# untitled.net
KiCad netlist of a schematic drawn in EAGLE
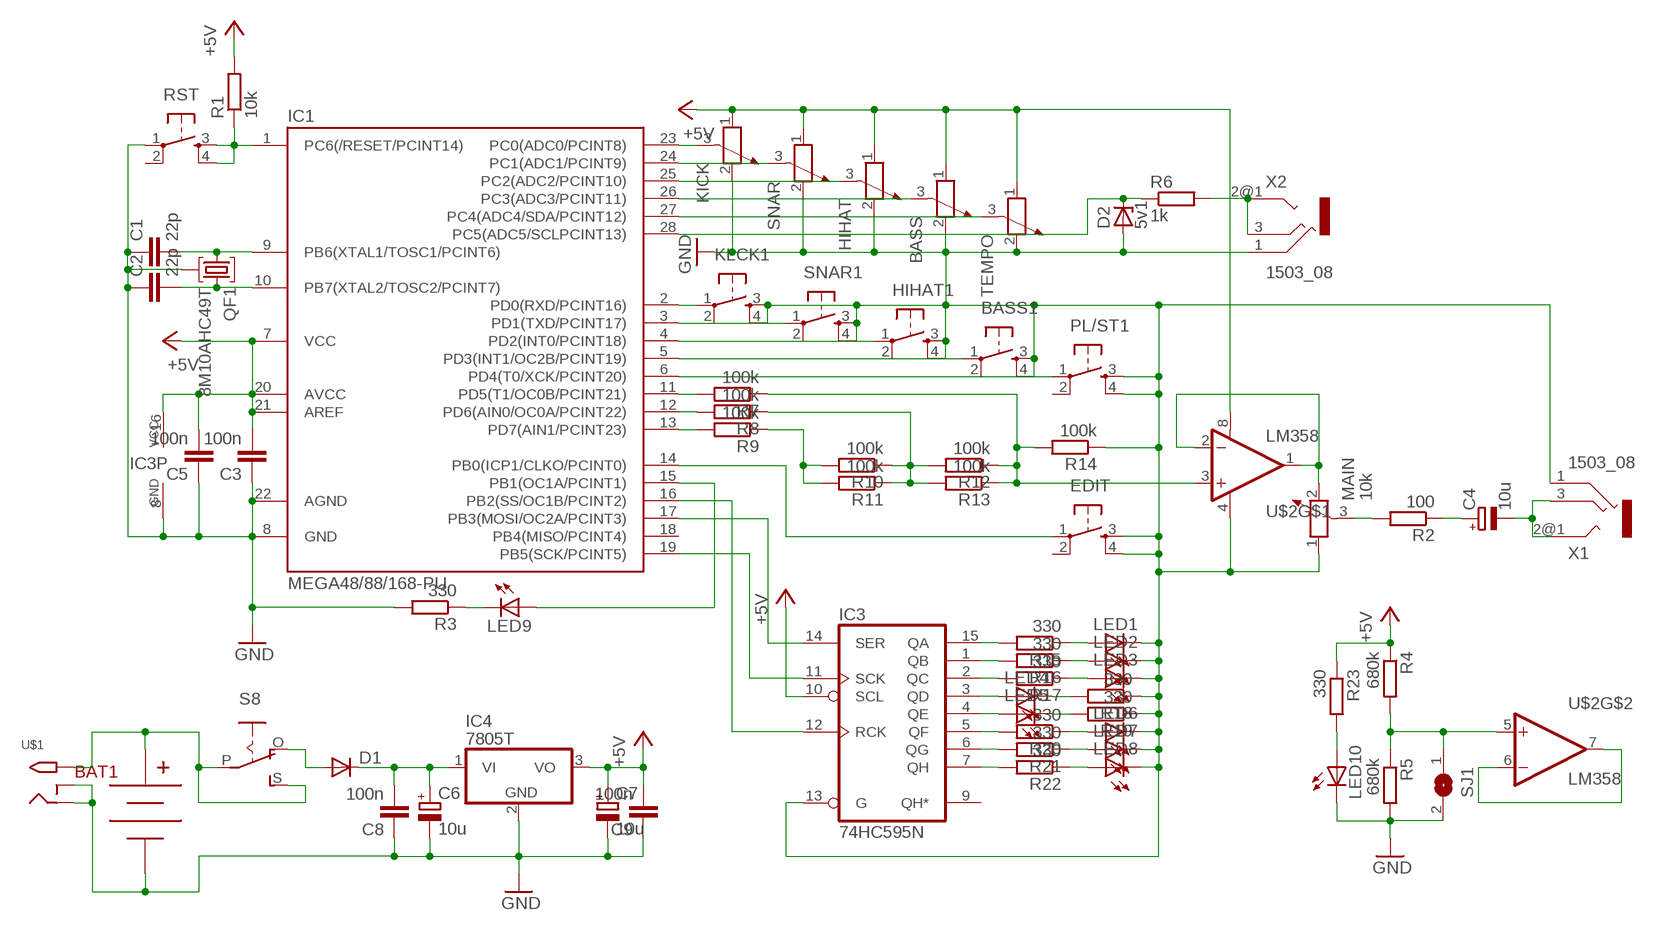
[diagram p0: schematic, sheet 1]

(export (version "E")
  (design (tool "Eeschema 10.0.6"))
  (components
    (comp (ref "BASS")
      (value "POTENTIOMETER_PT-10")
      (footprint "eagle-import:PT-10")
      (libsource (lib "eagle-import") (part "POTENTIOMETER_PT-10"))
    )
    (comp (ref "BASS1")
      (value "TAC_SWITCHPTH")
      (footprint "eagle-import:TACTILE-PTH")
      (libsource (lib "eagle-import") (part "TAC_SWITCHPTH"))
    )
    (comp (ref "BAT1")
      (value "BC9VPC")
      (footprint "eagle-import:BC9VPC")
      (libsource (lib "eagle-import") (part "BC9VPC"))
    )
    (comp (ref "C1")
      (value "22p")
      (footprint "eagle-import:C025-025X050")
      (libsource (lib "eagle-import") (part "C-EU025-025X050"))
    )
    (comp (ref "C2")
      (value "22p")
      (footprint "eagle-import:C025-025X050")
      (libsource (lib "eagle-import") (part "C-EU025-025X050"))
    )
    (comp (ref "C3")
      (value "100n")
      (footprint "eagle-import:C025-025X050")
      (libsource (lib "eagle-import") (part "C-EU025-025X050"))
    )
    (comp (ref "C4")
      (value "10u")
      (footprint "eagle-import:E2,5-6")
      (libsource (lib "eagle-import") (part "CPOL-EUE2.5-6"))
    )
    (comp (ref "C5")
      (value "100n")
      (footprint "eagle-import:C025-025X050")
      (libsource (lib "eagle-import") (part "C-EU025-025X050"))
    )
    (comp (ref "C6")
      (value "10u")
      (footprint "eagle-import:E2,5-5")
      (libsource (lib "eagle-import") (part "CPOL-EUE2.5-5"))
    )
    (comp (ref "C7")
      (value "10u")
      (footprint "eagle-import:E2,5-5")
      (libsource (lib "eagle-import") (part "CPOL-EUE2.5-5"))
    )
    (comp (ref "C8")
      (value "100n")
      (footprint "eagle-import:C025-025X050")
      (libsource (lib "eagle-import") (part "C-EU025-025X050"))
    )
    (comp (ref "C9")
      (value "100n")
      (footprint "eagle-import:C025-025X050")
      (libsource (lib "eagle-import") (part "C-EU025-025X050"))
    )
    (comp (ref "D1")
      (value "DIODE-D-5")
      (footprint "eagle-import:D-5")
      (libsource (lib "eagle-import") (part "DIODE-D-5"))
    )
    (comp (ref "D2")
      (value "5v1")
      (footprint "eagle-import:ZDIO-2.5")
      (libsource (lib "eagle-import") (part "ZENER-DIODEZD-2.5"))
    )
    (comp (ref "EDIT")
      (value "TAC_SWITCHPTH")
      (footprint "eagle-import:TACTILE-PTH")
      (libsource (lib "eagle-import") (part "TAC_SWITCHPTH"))
    )
    (comp (ref "HIHAT")
      (value "POTENTIOMETER_PT-10")
      (footprint "eagle-import:PT-10")
      (libsource (lib "eagle-import") (part "POTENTIOMETER_PT-10"))
    )
    (comp (ref "HIHAT1")
      (value "TAC_SWITCHPTH")
      (footprint "eagle-import:TACTILE-PTH")
      (libsource (lib "eagle-import") (part "TAC_SWITCHPTH"))
    )
    (comp (ref "IC1")
      (value "MEGA48/88/168-PU")
      (footprint "eagle-import:DIL28-3")
      (libsource (lib "eagle-import") (part "MEGA48/88/168-PU"))
    )
    (comp (ref "IC3")
      (value "74HC595N")
      (footprint "eagle-import:DIL16")
      (libsource (lib "eagle-import") (part "74595NHC"))
    )
    (comp (ref "IC4")
      (value "7805T")
      (footprint "eagle-import:TO220H")
      (libsource (lib "eagle-import") (part "78T05"))
    )
    (comp (ref "KICK")
      (value "POTENTIOMETER_PT-10")
      (footprint "eagle-import:PT-10")
      (libsource (lib "eagle-import") (part "POTENTIOMETER_PT-10"))
    )
    (comp (ref "KLCK1")
      (value "TAC_SWITCHPTH")
      (footprint "eagle-import:TACTILE-PTH")
      (libsource (lib "eagle-import") (part "TAC_SWITCHPTH"))
    )
    (comp (ref "LED1")
      (value "LED5MM")
      (footprint "eagle-import:LED5MM")
      (libsource (lib "eagle-import") (part "LED5MM"))
    )
    (comp (ref "LED2")
      (value "LED5MM")
      (footprint "eagle-import:LED5MM")
      (libsource (lib "eagle-import") (part "LED5MM"))
    )
    (comp (ref "LED3")
      (value "LED5MM")
      (footprint "eagle-import:LED5MM")
      (libsource (lib "eagle-import") (part "LED5MM"))
    )
    (comp (ref "LED4")
      (value "LED5MM")
      (footprint "eagle-import:LED5MM")
      (libsource (lib "eagle-import") (part "LED5MM"))
    )
    (comp (ref "LED5")
      (value "LED5MM")
      (footprint "eagle-import:LED5MM")
      (libsource (lib "eagle-import") (part "LED5MM"))
    )
    (comp (ref "LED6")
      (value "LED5MM")
      (footprint "eagle-import:LED5MM")
      (libsource (lib "eagle-import") (part "LED5MM"))
    )
    (comp (ref "LED7")
      (value "LED5MM")
      (footprint "eagle-import:LED5MM")
      (libsource (lib "eagle-import") (part "LED5MM"))
    )
    (comp (ref "LED8")
      (value "LED5MM")
      (footprint "eagle-import:LED5MM")
      (libsource (lib "eagle-import") (part "LED5MM"))
    )
    (comp (ref "LED9")
      (value "LED5MM")
      (footprint "eagle-import:LED5MM")
      (libsource (lib "eagle-import") (part "LED5MM"))
    )
    (comp (ref "LED10")
      (value "LED5MM")
      (footprint "eagle-import:LED5MM")
      (libsource (lib "eagle-import") (part "LED5MM"))
    )
    (comp (ref "MAIN")
      (value "10k")
      (footprint "eagle-import:PT-10")
      (libsource (lib "eagle-import") (part "POTENTIOMETER_PT-10"))
    )
    (comp (ref "PL/ST1")
      (value "TAC_SWITCHPTH")
      (footprint "eagle-import:TACTILE-PTH")
      (libsource (lib "eagle-import") (part "TAC_SWITCHPTH"))
    )
    (comp (ref "QF1")
      (value "8M10AHC49T")
      (footprint "eagle-import:HC49U")
      (libsource (lib "eagle-import") (part "8M10AHC49T"))
    )
    (comp (ref "R1")
      (value "10k")
      (footprint "eagle-import:0204_7")
      (libsource (lib "eagle-import") (part "R-EU_0204/7"))
    )
    (comp (ref "R2")
      (value "100")
      (footprint "eagle-import:0204_7")
      (libsource (lib "eagle-import") (part "R-EU_0204/7"))
    )
    (comp (ref "R3")
      (value "330")
      (footprint "eagle-import:0204_7")
      (libsource (lib "eagle-import") (part "R-EU_0204/7"))
    )
    (comp (ref "R4")
      (value "680k")
      (footprint "eagle-import:0204_5")
      (libsource (lib "eagle-import") (part "R-EU_0204/5"))
    )
    (comp (ref "R5")
      (value "680k")
      (footprint "eagle-import:0204_7")
      (libsource (lib "eagle-import") (part "R-EU_0204/7"))
    )
    (comp (ref "R6")
      (value "1k")
      (footprint "eagle-import:0204_7")
      (libsource (lib "eagle-import") (part "R-EU_0204/7"))
    )
    (comp (ref "R7")
      (value "100k")
      (footprint "eagle-import:0204_7")
      (libsource (lib "eagle-import") (part "R-EU_0204/7"))
    )
    (comp (ref "R8")
      (value "100k")
      (footprint "eagle-import:0204_7")
      (libsource (lib "eagle-import") (part "R-EU_0204/7"))
    )
    (comp (ref "R9")
      (value "100k")
      (footprint "eagle-import:0204_7")
      (libsource (lib "eagle-import") (part "R-EU_0204/7"))
    )
    (comp (ref "R10")
      (value "100k")
      (footprint "eagle-import:0204_7")
      (libsource (lib "eagle-import") (part "R-EU_0204/7"))
    )
    (comp (ref "R11")
      (value "100k")
      (footprint "eagle-import:0204_7")
      (libsource (lib "eagle-import") (part "R-EU_0204/7"))
    )
    (comp (ref "R12")
      (value "100k")
      (footprint "eagle-import:0204_7")
      (libsource (lib "eagle-import") (part "R-EU_0204/7"))
    )
    (comp (ref "R13")
      (value "100k")
      (footprint "eagle-import:0204_7")
      (libsource (lib "eagle-import") (part "R-EU_0204/7"))
    )
    (comp (ref "R14")
      (value "100k")
      (footprint "eagle-import:0204_7")
      (libsource (lib "eagle-import") (part "R-EU_0204/7"))
    )
    (comp (ref "R15")
      (value "330")
      (footprint "eagle-import:0204_7")
      (libsource (lib "eagle-import") (part "R-EU_0204/7"))
    )
    (comp (ref "R16")
      (value "330")
      (footprint "eagle-import:0204_7")
      (libsource (lib "eagle-import") (part "R-EU_0204/7"))
    )
    (comp (ref "R17")
      (value "330")
      (footprint "eagle-import:0204_7")
      (libsource (lib "eagle-import") (part "R-EU_0204/7"))
    )
    (comp (ref "R18")
      (value "330")
      (footprint "eagle-import:0204_7")
      (libsource (lib "eagle-import") (part "R-EU_0204/7"))
    )
    (comp (ref "R19")
      (value "330")
      (footprint "eagle-import:0204_7")
      (libsource (lib "eagle-import") (part "R-EU_0204/7"))
    )
    (comp (ref "R20")
      (value "330")
      (footprint "eagle-import:0204_7")
      (libsource (lib "eagle-import") (part "R-EU_0204/7"))
    )
    (comp (ref "R21")
      (value "330")
      (footprint "eagle-import:0204_7")
      (libsource (lib "eagle-import") (part "R-EU_0204/7"))
    )
    (comp (ref "R22")
      (value "330")
      (footprint "eagle-import:0204_7")
      (libsource (lib "eagle-import") (part "R-EU_0204/7"))
    )
    (comp (ref "R23")
      (value "330")
      (footprint "eagle-import:0204_5")
      (libsource (lib "eagle-import") (part "R-EU_0204/5"))
    )
    (comp (ref "RST")
      (value "TAC_SWITCHPTH")
      (footprint "eagle-import:TACTILE-PTH")
      (libsource (lib "eagle-import") (part "TAC_SWITCHPTH"))
    )
    (comp (ref "S8")
      (value "EG1218S")
      (footprint "eagle-import:EG1218")
      (libsource (lib "eagle-import") (part "EG1218S"))
    )
    (comp (ref "SJ1") (value "SJ") (footprint "eagle-import:SJ") (libsource (lib "eagle-import") (part "SJ")))
    (comp (ref "SNAR")
      (value "POTENTIOMETER_PT-10")
      (footprint "eagle-import:PT-10")
      (libsource (lib "eagle-import") (part "POTENTIOMETER_PT-10"))
    )
    (comp (ref "SNAR1")
      (value "TAC_SWITCHPTH")
      (footprint "eagle-import:TACTILE-PTH")
      (libsource (lib "eagle-import") (part "TAC_SWITCHPTH"))
    )
    (comp (ref "TEMPO")
      (value "POTENTIOMETER_PT-10")
      (footprint "eagle-import:PT-10")
      (libsource (lib "eagle-import") (part "POTENTIOMETER_PT-10"))
    )
    (comp (ref "U$1")
      (value "2.1MMJACKTHM")
      (footprint "eagle-import:PJ-102A")
      (libsource (lib "eagle-import") (part "2.1MMJACKTHM"))
    )
    (comp (ref "U$2")
      (value "LM358")
      (footprint "eagle-import:DIP08")
      (libsource (lib "eagle-import") (part "LM358"))
    )
    (comp (ref "X1")
      (value "1503_08")
      (footprint "eagle-import:1503_08")
      (libsource (lib "eagle-import") (part "1503_?08"))
    )
    (comp (ref "X2")
      (value "1503_08")
      (footprint "eagle-import:1503_08")
      (fields (field (name "OC_FARNELL") "unknown") (field (name "OC_NEWARK") "unknown"))
      (libsource (lib "eagle-import") (part "1503_?08"))
    )
  )
  (nets
    (net (code "1") (name "+5V") (class "Default")
      (node (ref "BASS") (pin "1") (pinfunction "1_1") (pintype "passive"))
      (node (ref "C3") (pin "2") (pinfunction "2_2") (pintype "passive"))
      (node (ref "C5") (pin "2") (pinfunction "2_2") (pintype "passive"))
      (node (ref "C7") (pin "+") (pinfunction "+_+") (pintype "passive"))
      (node (ref "C9") (pin "2") (pinfunction "2_2") (pintype "passive"))
      (node (ref "HIHAT") (pin "1") (pinfunction "1_1") (pintype "passive"))
      (node (ref "IC1") (pin "20") (pinfunction "AVCC_20") (pintype "passive"))
      (node (ref "IC1") (pin "21") (pinfunction "AREF_21") (pintype "passive"))
      (node (ref "IC1") (pin "7") (pinfunction "VCC_7") (pintype "power_in"))
      (node (ref "IC3") (pin "10") (pinfunction "SCL_10") (pintype "input"))
      (node (ref "IC3") (pin "16") (pinfunction "VCC_16") (pintype "power_in"))
      (node (ref "IC4") (pin "3") (pinfunction "VO_3") (pintype "passive"))
      (node (ref "KICK") (pin "1") (pinfunction "1_1") (pintype "passive"))
      (node (ref "R1") (pin "2") (pinfunction "2_2") (pintype "passive"))
      (node (ref "R23") (pin "1") (pinfunction "1_1") (pintype "passive"))
      (node (ref "R4") (pin "1") (pinfunction "1_1") (pintype "passive"))
      (node (ref "SNAR") (pin "1") (pinfunction "1_1") (pintype "passive"))
      (node (ref "TEMPO") (pin "1") (pinfunction "1_1") (pintype "passive"))
      (node (ref "U$2") (pin "8") (pinfunction "V+_8") (pintype "power_in"))
    )
    (net (code "2") (name "GND") (class "Default")
      (node (ref "BASS") (pin "2") (pinfunction "2_2") (pintype "passive"))
      (node (ref "BASS1") (pin "3") (pinfunction "3_3") (pintype "passive"))
      (node (ref "BASS1") (pin "4") (pinfunction "4_4") (pintype "passive"))
      (node (ref "BAT1") (pin "V-") (pinfunction "V-_V-") (pintype "bidirectional"))
      (node (ref "C1") (pin "1") (pinfunction "1_1") (pintype "passive"))
      (node (ref "C2") (pin "1") (pinfunction "1_1") (pintype "passive"))
      (node (ref "C3") (pin "1") (pinfunction "1_1") (pintype "passive"))
      (node (ref "C5") (pin "1") (pinfunction "1_1") (pintype "passive"))
      (node (ref "C6") (pin "-") (pinfunction "-_-") (pintype "passive"))
      (node (ref "C7") (pin "-") (pinfunction "-_-") (pintype "passive"))
      (node (ref "C8") (pin "1") (pinfunction "1_1") (pintype "passive"))
      (node (ref "C9") (pin "1") (pinfunction "1_1") (pintype "passive"))
      (node (ref "D2") (pin "A") (pinfunction "A_A") (pintype "passive"))
      (node (ref "EDIT") (pin "3") (pinfunction "3_3") (pintype "passive"))
      (node (ref "EDIT") (pin "4") (pinfunction "4_4") (pintype "passive"))
      (node (ref "HIHAT") (pin "2") (pinfunction "2_2") (pintype "passive"))
      (node (ref "HIHAT1") (pin "3") (pinfunction "3_3") (pintype "passive"))
      (node (ref "HIHAT1") (pin "4") (pinfunction "4_4") (pintype "passive"))
      (node (ref "IC1") (pin "22") (pinfunction "AGND_22") (pintype "power_in"))
      (node (ref "IC1") (pin "8") (pinfunction "GND_8") (pintype "power_in"))
      (node (ref "IC3") (pin "13") (pinfunction "G_13") (pintype "input"))
      (node (ref "IC3") (pin "8") (pinfunction "GND_8") (pintype "power_in"))
      (node (ref "IC4") (pin "2") (pinfunction "GND_2") (pintype "passive"))
      (node (ref "KICK") (pin "2") (pinfunction "2_2") (pintype "passive"))
      (node (ref "KLCK1") (pin "3") (pinfunction "3_3") (pintype "passive"))
      (node (ref "KLCK1") (pin "4") (pinfunction "4_4") (pintype "passive"))
      (node (ref "LED1") (pin "K") (pinfunction "C_K") (pintype "passive"))
      (node (ref "LED10") (pin "K") (pinfunction "C_K") (pintype "passive"))
      (node (ref "LED2") (pin "K") (pinfunction "C_K") (pintype "passive"))
      (node (ref "LED3") (pin "K") (pinfunction "C_K") (pintype "passive"))
      (node (ref "LED6") (pin "K") (pinfunction "C_K") (pintype "passive"))
      (node (ref "LED7") (pin "K") (pinfunction "C_K") (pintype "passive"))
      (node (ref "LED8") (pin "K") (pinfunction "C_K") (pintype "passive"))
      (node (ref "MAIN") (pin "1") (pinfunction "1_1") (pintype "passive"))
      (node (ref "PL/ST1") (pin "3") (pinfunction "3_3") (pintype "passive"))
      (node (ref "PL/ST1") (pin "4") (pinfunction "4_4") (pintype "passive"))
      (node (ref "QF1") (pin "2") (pinfunction "2_2") (pintype "passive"))
      (node (ref "R14") (pin "1") (pinfunction "1_1") (pintype "passive"))
      (node (ref "R18") (pin "1") (pinfunction "1_1") (pintype "passive"))
      (node (ref "R19") (pin "1") (pinfunction "1_1") (pintype "passive"))
      (node (ref "R3") (pin "2") (pinfunction "2_2") (pintype "passive"))
      (node (ref "R5") (pin "2") (pinfunction "2_2") (pintype "passive"))
      (node (ref "RST") (pin "1") (pinfunction "1_1") (pintype "passive"))
      (node (ref "SJ1") (pin "2") (pinfunction "2_2") (pintype "passive"))
      (node (ref "SNAR") (pin "2") (pinfunction "2_2") (pintype "passive"))
      (node (ref "SNAR1") (pin "3") (pinfunction "3_3") (pintype "passive"))
      (node (ref "SNAR1") (pin "4") (pinfunction "4_4") (pintype "passive"))
      (node (ref "TEMPO") (pin "2") (pinfunction "2_2") (pintype "passive"))
      (node (ref "U$1") (pin "RING") (pinfunction "RING_RING") (pintype "bidirectional"))
      (node (ref "U$1") (pin "RING_SW") (pinfunction "RING_SW_RING_SW") (pintype "bidirectional"))
      (node (ref "U$2") (pin "4") (pinfunction "V-_4") (pintype "power_in"))
      (node (ref "X1") (pin "1") (pinfunction "1_1") (pintype "passive"))
      (node (ref "X2") (pin "1") (pinfunction "1_1") (pintype "passive"))
    )
    (net (code "3") (name "Net-(BAT1-PadV+)") (class "Default")
      (node (ref "BAT1") (pin "V+") (pinfunction "V+_V+") (pintype "bidirectional"))
      (node (ref "S8") (pin "P") (pinfunction "P_P") (pintype "passive"))
      (node (ref "S8") (pin "S") (pinfunction "S_S") (pintype "passive"))
      (node (ref "U$1") (pin "TIP") (pinfunction "TIP_TIP") (pintype "bidirectional"))
    )
    (net (code "4") (name "Net-(C4-Pad+)") (class "Default")
      (node (ref "C4") (pin "+") (pinfunction "+_+") (pintype "passive"))
      (node (ref "R2") (pin "1") (pinfunction "1_1") (pintype "passive"))
    )
    (net (code "5") (name "Net-(C4-Pad-)") (class "Default")
      (node (ref "C4") (pin "-") (pinfunction "-_-") (pintype "passive"))
      (node (ref "X1") (pin "2@1") (pinfunction "2_2@1") (pintype "passive"))
      (node (ref "X1") (pin "3") (pinfunction "3_3") (pintype "passive"))
    )
    (net (code "6") (name "Net-(D1-PadA)") (class "Default")
      (node (ref "D1") (pin "A") (pinfunction "A_A") (pintype "passive"))
      (node (ref "S8") (pin "O") (pinfunction "O_O") (pintype "passive"))
    )
    (net (code "7") (name "Net-(IC1-PB0(ICP1{slash}CLKO{slash}PCINT0))") (class "Default")
      (node (ref "EDIT") (pin "1") (pinfunction "1_1") (pintype "passive"))
      (node (ref "IC1") (pin "14") (pinfunction "PB0(ICP1/CLKO/PCINT0)_14") (pintype "bidirectional"))
    )
    (net (code "8") (name "Net-(IC1-PB1(OC1A{slash}PCINT1))") (class "Default")
      (node (ref "IC1") (pin "15") (pinfunction "PB1(OC1A/PCINT1)_15") (pintype "bidirectional"))
      (node (ref "LED9") (pin "A") (pinfunction "A_A") (pintype "passive"))
    )
    (net (code "9") (name "Net-(IC1-PB2(SS{slash}OC1B{slash}PCINT2))") (class "Default")
      (node (ref "IC1") (pin "16") (pinfunction "PB2(SS/OC1B/PCINT2)_16") (pintype "bidirectional"))
      (node (ref "IC3") (pin "12") (pinfunction "RCK_12") (pintype "input"))
    )
    (net (code "10") (name "Net-(IC1-PB3(MOSI{slash}OC2A{slash}PCINT3))") (class "Default")
      (node (ref "IC1") (pin "17") (pinfunction "PB3(MOSI/OC2A/PCINT3)_17") (pintype "bidirectional"))
      (node (ref "IC3") (pin "14") (pinfunction "SER_14") (pintype "input"))
    )
    (net (code "11") (name "Net-(IC1-PB5(SCK{slash}PCINT5))") (class "Default")
      (node (ref "IC1") (pin "19") (pinfunction "PB5(SCK/PCINT5)_19") (pintype "bidirectional"))
      (node (ref "IC3") (pin "11") (pinfunction "SCK_11") (pintype "input"))
    )
    (net (code "12") (name "Net-(IC1-PB6(XTAL1{slash}TOSC1{slash}PCINT6))") (class "Default")
      (node (ref "C1") (pin "2") (pinfunction "2_2") (pintype "passive"))
      (node (ref "IC1") (pin "9") (pinfunction "PB6(XTAL1/TOSC1/PCINT6)_9") (pintype "bidirectional"))
      (node (ref "QF1") (pin "1") (pinfunction "1_1") (pintype "passive"))
    )
    (net (code "13") (name "Net-(IC1-PB7(XTAL2{slash}TOSC2{slash}PCINT7))") (class "Default")
      (node (ref "C2") (pin "2") (pinfunction "2_2") (pintype "passive"))
      (node (ref "IC1") (pin "10") (pinfunction "PB7(XTAL2/TOSC2/PCINT7)_10") (pintype "bidirectional"))
      (node (ref "QF1") (pin "3") (pinfunction "3_3") (pintype "passive"))
    )
    (net (code "14") (name "Net-(IC1-PC0(ADC0{slash}PCINT8))") (class "Default")
      (node (ref "IC1") (pin "23") (pinfunction "PC0(ADC0/PCINT8)_23") (pintype "bidirectional"))
      (node (ref "KICK") (pin "3") (pinfunction "3_3") (pintype "passive"))
    )
    (net (code "15") (name "Net-(IC1-PC1(ADC1{slash}PCINT9))") (class "Default")
      (node (ref "IC1") (pin "24") (pinfunction "PC1(ADC1/PCINT9)_24") (pintype "bidirectional"))
      (node (ref "SNAR") (pin "3") (pinfunction "3_3") (pintype "passive"))
    )
    (net (code "16") (name "Net-(IC1-PC2(ADC2{slash}PCINT10))") (class "Default")
      (node (ref "HIHAT") (pin "3") (pinfunction "3_3") (pintype "passive"))
      (node (ref "IC1") (pin "25") (pinfunction "PC2(ADC2/PCINT10)_25") (pintype "bidirectional"))
    )
    (net (code "17") (name "Net-(IC1-PC3(ADC3{slash}PCINT11))") (class "Default")
      (node (ref "BASS") (pin "3") (pinfunction "3_3") (pintype "passive"))
      (node (ref "IC1") (pin "26") (pinfunction "PC3(ADC3/PCINT11)_26") (pintype "bidirectional"))
    )
    (net (code "18") (name "Net-(IC1-PC4(ADC4{slash}SDA{slash}PCINT12))") (class "Default")
      (node (ref "IC1") (pin "27") (pinfunction "PC4(ADC4/SDA/PCINT12)_27") (pintype "bidirectional"))
      (node (ref "TEMPO") (pin "3") (pinfunction "3_3") (pintype "passive"))
    )
    (net (code "19") (name "Net-(IC1-PC5(ADC5{slash}SCLPCINT13))") (class "Default")
      (node (ref "D2") (pin "C") (pinfunction "C_C") (pintype "passive"))
      (node (ref "IC1") (pin "28") (pinfunction "PC5(ADC5/SCLPCINT13)_28") (pintype "bidirectional"))
      (node (ref "R6") (pin "1") (pinfunction "1_1") (pintype "passive"))
    )
    (net (code "20") (name "Net-(IC1-PC6({slash}RESET{slash}PCINT14))") (class "Default")
      (node (ref "IC1") (pin "1") (pinfunction "PC6(/RESET/PCINT14)_1") (pintype "bidirectional"))
      (node (ref "R1") (pin "1") (pinfunction "1_1") (pintype "passive"))
      (node (ref "RST") (pin "3") (pinfunction "3_3") (pintype "passive"))
      (node (ref "RST") (pin "4") (pinfunction "4_4") (pintype "passive"))
    )
    (net (code "21") (name "Net-(IC1-PD0(RXD{slash}PCINT16))") (class "Default")
      (node (ref "IC1") (pin "2") (pinfunction "PD0(RXD/PCINT16)_2") (pintype "bidirectional"))
      (node (ref "KLCK1") (pin "1") (pinfunction "1_1") (pintype "passive"))
    )
    (net (code "22") (name "Net-(IC1-PD1(TXD{slash}PCINT17))") (class "Default")
      (node (ref "IC1") (pin "3") (pinfunction "PD1(TXD/PCINT17)_3") (pintype "bidirectional"))
      (node (ref "SNAR1") (pin "1") (pinfunction "1_1") (pintype "passive"))
    )
    (net (code "23") (name "Net-(IC1-PD2(INT0{slash}PCINT18))") (class "Default")
      (node (ref "HIHAT1") (pin "1") (pinfunction "1_1") (pintype "passive"))
      (node (ref "IC1") (pin "4") (pinfunction "PD2(INT0/PCINT18)_4") (pintype "bidirectional"))
    )
    (net (code "24") (name "Net-(IC1-PD3(INT1{slash}OC2B{slash}PCINT19))") (class "Default")
      (node (ref "BASS1") (pin "1") (pinfunction "1_1") (pintype "passive"))
      (node (ref "IC1") (pin "5") (pinfunction "PD3(INT1/OC2B/PCINT19)_5") (pintype "bidirectional"))
    )
    (net (code "25") (name "Net-(IC1-PD4(T0{slash}XCK{slash}PCINT20))") (class "Default")
      (node (ref "IC1") (pin "6") (pinfunction "PD4(T0/XCK/PCINT20)_6") (pintype "bidirectional"))
      (node (ref "PL/ST1") (pin "1") (pinfunction "1_1") (pintype "passive"))
    )
    (net (code "26") (name "Net-(IC1-PD5(T1{slash}OC0B{slash}PCINT21))") (class "Default")
      (node (ref "IC1") (pin "11") (pinfunction "PD5(T1/OC0B/PCINT21)_11") (pintype "bidirectional"))
      (node (ref "R7") (pin "2") (pinfunction "2_2") (pintype "passive"))
    )
    (net (code "27") (name "Net-(IC1-PD6(AIN0{slash}OC0A{slash}PCINT22))") (class "Default")
      (node (ref "IC1") (pin "12") (pinfunction "PD6(AIN0/OC0A/PCINT22)_12") (pintype "bidirectional"))
      (node (ref "R8") (pin "2") (pinfunction "2_2") (pintype "passive"))
    )
    (net (code "28") (name "Net-(IC1-PD7(AIN1{slash}PCINT23))") (class "Default")
      (node (ref "IC1") (pin "13") (pinfunction "PD7(AIN1/PCINT23)_13") (pintype "bidirectional"))
      (node (ref "R9") (pin "2") (pinfunction "2_2") (pintype "passive"))
    )
    (net (code "29") (name "Net-(IC3A-QA)") (class "Default")
      (node (ref "IC3") (pin "15") (pinfunction "QA_15") (pintype "tri_state"))
      (node (ref "R15") (pin "2") (pinfunction "2_2") (pintype "passive"))
    )
    (net (code "30") (name "Net-(IC3A-QB)") (class "Default")
      (node (ref "IC3") (pin "1") (pinfunction "QB_1") (pintype "tri_state"))
      (node (ref "R16") (pin "2") (pinfunction "2_2") (pintype "passive"))
    )
    (net (code "31") (name "Net-(IC3A-QC)") (class "Default")
      (node (ref "IC3") (pin "2") (pinfunction "QC_2") (pintype "tri_state"))
      (node (ref "R17") (pin "2") (pinfunction "2_2") (pintype "passive"))
    )
    (net (code "32") (name "Net-(IC3A-QD)") (class "Default")
      (node (ref "IC3") (pin "3") (pinfunction "QD_3") (pintype "tri_state"))
      (node (ref "LED4") (pin "A") (pinfunction "A_A") (pintype "passive"))
    )
    (net (code "33") (name "Net-(IC3A-QE)") (class "Default")
      (node (ref "IC3") (pin "4") (pinfunction "QE_4") (pintype "tri_state"))
      (node (ref "LED5") (pin "A") (pinfunction "A_A") (pintype "passive"))
    )
    (net (code "34") (name "Net-(IC3A-QF)") (class "Default")
      (node (ref "IC3") (pin "5") (pinfunction "QF_5") (pintype "tri_state"))
      (node (ref "R20") (pin "2") (pinfunction "2_2") (pintype "passive"))
    )
    (net (code "35") (name "Net-(IC3A-QG)") (class "Default")
      (node (ref "IC3") (pin "6") (pinfunction "QG_6") (pintype "tri_state"))
      (node (ref "R21") (pin "2") (pinfunction "2_2") (pintype "passive"))
    )
    (net (code "36") (name "Net-(IC3A-QH)") (class "Default")
      (node (ref "IC3") (pin "7") (pinfunction "QH_7") (pintype "tri_state"))
      (node (ref "R22") (pin "2") (pinfunction "2_2") (pintype "passive"))
    )
    (net (code "37") (name "Net-(IC4-VI)") (class "Default")
      (node (ref "C6") (pin "+") (pinfunction "+_+") (pintype "passive"))
      (node (ref "C8") (pin "2") (pinfunction "2_2") (pintype "passive"))
      (node (ref "D1") (pin "C") (pinfunction "C_C") (pintype "passive"))
      (node (ref "IC4") (pin "1") (pinfunction "VI_1") (pintype "input"))
    )
    (net (code "38") (name "Net-(LED1-PadA)") (class "Default")
      (node (ref "LED1") (pin "A") (pinfunction "A_A") (pintype "passive"))
      (node (ref "R15") (pin "1") (pinfunction "1_1") (pintype "passive"))
    )
    (net (code "39") (name "Net-(LED2-PadA)") (class "Default")
      (node (ref "LED2") (pin "A") (pinfunction "A_A") (pintype "passive"))
      (node (ref "R16") (pin "1") (pinfunction "1_1") (pintype "passive"))
    )
    (net (code "40") (name "Net-(LED3-PadA)") (class "Default")
      (node (ref "LED3") (pin "A") (pinfunction "A_A") (pintype "passive"))
      (node (ref "R17") (pin "1") (pinfunction "1_1") (pintype "passive"))
    )
    (net (code "41") (name "Net-(LED4-C)") (class "Default")
      (node (ref "LED4") (pin "K") (pinfunction "C_K") (pintype "passive"))
      (node (ref "R18") (pin "2") (pinfunction "2_2") (pintype "passive"))
    )
    (net (code "42") (name "Net-(LED5-C)") (class "Default")
      (node (ref "LED5") (pin "K") (pinfunction "C_K") (pintype "passive"))
      (node (ref "R19") (pin "2") (pinfunction "2_2") (pintype "passive"))
    )
    (net (code "43") (name "Net-(LED6-PadA)") (class "Default")
      (node (ref "LED6") (pin "A") (pinfunction "A_A") (pintype "passive"))
      (node (ref "R20") (pin "1") (pinfunction "1_1") (pintype "passive"))
    )
    (net (code "44") (name "Net-(LED7-PadA)") (class "Default")
      (node (ref "LED7") (pin "A") (pinfunction "A_A") (pintype "passive"))
      (node (ref "R21") (pin "1") (pinfunction "1_1") (pintype "passive"))
    )
    (net (code "45") (name "Net-(LED8-PadA)") (class "Default")
      (node (ref "LED8") (pin "A") (pinfunction "A_A") (pintype "passive"))
      (node (ref "R22") (pin "1") (pinfunction "1_1") (pintype "passive"))
    )
    (net (code "46") (name "Net-(LED9-C)") (class "Default")
      (node (ref "LED9") (pin "K") (pinfunction "C_K") (pintype "passive"))
      (node (ref "R3") (pin "1") (pinfunction "1_1") (pintype "passive"))
    )
    (net (code "47") (name "Net-(LED10-PadA)") (class "Default")
      (node (ref "LED10") (pin "A") (pinfunction "A_A") (pintype "passive"))
      (node (ref "R23") (pin "2") (pinfunction "2_2") (pintype "passive"))
    )
    (net (code "48") (name "Net-(MAIN-Pad3)") (class "Default")
      (node (ref "MAIN") (pin "3") (pinfunction "3_3") (pintype "passive"))
      (node (ref "R2") (pin "2") (pinfunction "2_2") (pintype "passive"))
    )
    (net (code "49") (name "Net-(R6-Pad2)") (class "Default")
      (node (ref "R6") (pin "2") (pinfunction "2_2") (pintype "passive"))
      (node (ref "X2") (pin "2@1") (pinfunction "2_2@1") (pintype "passive"))
      (node (ref "X2") (pin "3") (pinfunction "3_3") (pintype "passive"))
    )
    (net (code "50") (name "Net-(R10-Pad1)") (class "Default")
      (node (ref "R10") (pin "1") (pinfunction "1_1") (pintype "passive"))
      (node (ref "R11") (pin "1") (pinfunction "1_1") (pintype "passive"))
      (node (ref "R12") (pin "2") (pinfunction "2_2") (pintype "passive"))
      (node (ref "R13") (pin "2") (pinfunction "2_2") (pintype "passive"))
      (node (ref "R8") (pin "1") (pinfunction "1_1") (pintype "passive"))
    )
    (net (code "51") (name "Net-(R10-Pad2)") (class "Default")
      (node (ref "R10") (pin "2") (pinfunction "2_2") (pintype "passive"))
      (node (ref "R11") (pin "2") (pinfunction "2_2") (pintype "passive"))
      (node (ref "R9") (pin "1") (pinfunction "1_1") (pintype "passive"))
    )
    (net (code "52") (name "Net-(U$2A-+IN)") (class "Default")
      (node (ref "R12") (pin "1") (pinfunction "1_1") (pintype "passive"))
      (node (ref "R13") (pin "1") (pinfunction "1_1") (pintype "passive"))
      (node (ref "R14") (pin "2") (pinfunction "2_2") (pintype "passive"))
      (node (ref "R7") (pin "1") (pinfunction "1_1") (pintype "passive"))
      (node (ref "U$2") (pin "3") (pinfunction "+IN_3") (pintype "input"))
    )
    (net (code "53") (name "Net-(U$2A--IN)") (class "Default")
      (node (ref "MAIN") (pin "2") (pinfunction "2_2") (pintype "passive"))
      (node (ref "U$2") (pin "1") (pinfunction "OUT_1") (pintype "output"))
      (node (ref "U$2") (pin "2") (pinfunction "-IN_2") (pintype "input"))
    )
    (net (code "54") (name "Net-(U$2B-+IN)") (class "Default")
      (node (ref "R4") (pin "2") (pinfunction "2_2") (pintype "passive"))
      (node (ref "R5") (pin "1") (pinfunction "1_1") (pintype "passive"))
      (node (ref "SJ1") (pin "1") (pinfunction "1_1") (pintype "passive"))
      (node (ref "U$2") (pin "5") (pinfunction "+IN_5") (pintype "input"))
    )
    (net (code "55") (name "Net-(U$2B--IN)") (class "Default")
      (node (ref "U$2") (pin "6") (pinfunction "-IN_6") (pintype "input"))
      (node (ref "U$2") (pin "7") (pinfunction "OUT_7") (pintype "output"))
    )
    (net (code "56") (name "unconnected-(BASS1-Pad2)") (class "Default")
      (node (ref "BASS1") (pin "2") (pinfunction "2_2") (pintype "passive"))
    )
    (net (code "57") (name "unconnected-(EDIT-Pad2)") (class "Default")
      (node (ref "EDIT") (pin "2") (pinfunction "2_2") (pintype "passive"))
    )
    (net (code "58") (name "unconnected-(HIHAT1-Pad2)") (class "Default")
      (node (ref "HIHAT1") (pin "2") (pinfunction "2_2") (pintype "passive"))
    )
    (net (code "59") (name "unconnected-(IC1-PB4(MISO{slash}PCINT4)-Pad18)") (class "Default")
      (node (ref "IC1") (pin "18") (pinfunction "PB4(MISO/PCINT4)_18") (pintype "bidirectional"))
    )
    (net (code "60") (name "unconnected-(IC3A-QH*-Pad9)") (class "Default")
      (node (ref "IC3") (pin "9") (pinfunction "QH*_9") (pintype "tri_state"))
    )
    (net (code "61") (name "unconnected-(KLCK1-Pad2)") (class "Default")
      (node (ref "KLCK1") (pin "2") (pinfunction "2_2") (pintype "passive"))
    )
    (net (code "62") (name "unconnected-(PL/ST1-Pad2)") (class "Default")
      (node (ref "PL/ST1") (pin "2") (pinfunction "2_2") (pintype "passive"))
    )
    (net (code "63") (name "unconnected-(RST-Pad2)") (class "Default")
      (node (ref "RST") (pin "2") (pinfunction "2_2") (pintype "passive"))
    )
    (net (code "64") (name "unconnected-(SNAR1-Pad2)") (class "Default")
      (node (ref "SNAR1") (pin "2") (pinfunction "2_2") (pintype "passive"))
    )
    (net (code "65") (name "unconnected-(X1-2-Pad2@2)") (class "Default")
      (node (ref "X1") (pin "2@2") (pinfunction "2_2@2") (pintype "passive"))
    )
    (net (code "66") (name "unconnected-(X2-2-Pad2@2)") (class "Default")
      (node (ref "X2") (pin "2@2") (pinfunction "2_2@2") (pintype "passive"))
    )
  )
)
